# POWER.net
KiCad netlist of a schematic drawn in Altium Designer
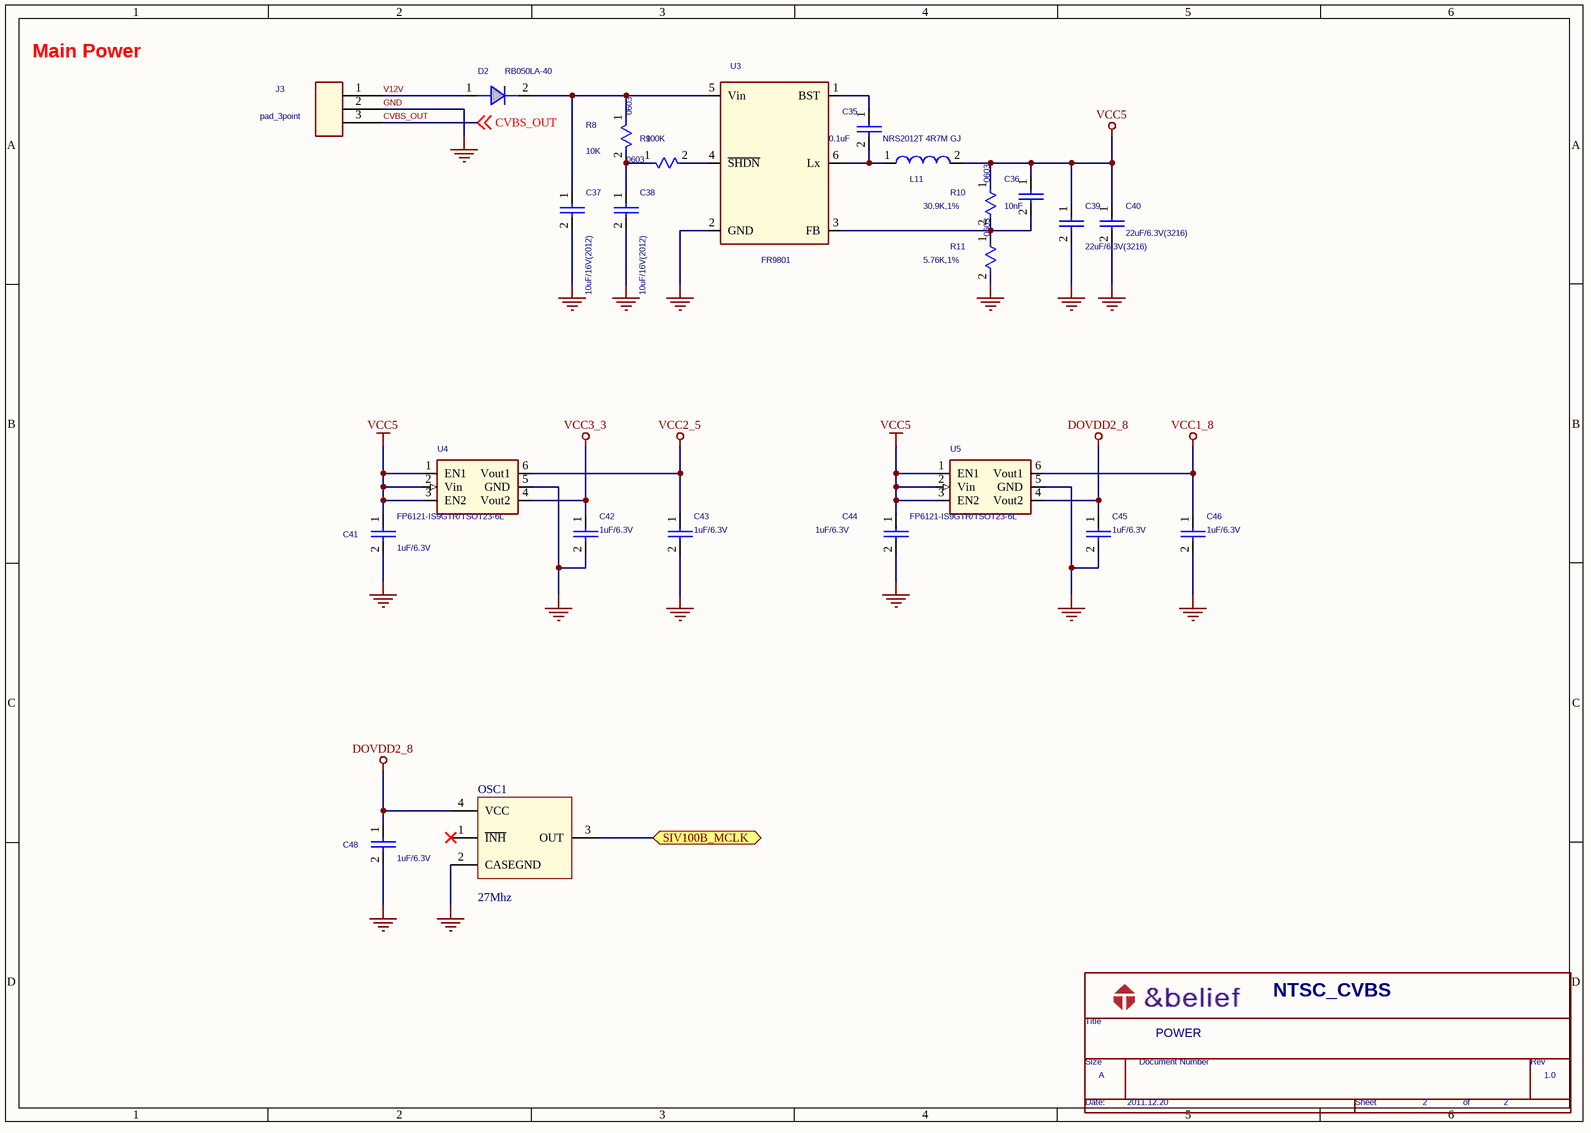
[diagram p0: POWER.SchDoc]

(export (version "E")
  (design (tool "Eeschema 10.0.6"))
  (components
    (comp (ref "C35") (value "0.1uF") (footprint "CAPC1005X55N") (libsource (lib "*") (part "CAP NP_16")))
    (comp (ref "C36") (value "10nF") (footprint "CAPC1005X55N") (libsource (lib "*") (part "CAP NP_13")))
    (comp (ref "C37")
      (value "10uF/16V(2012)")
      (footprint "CAPC2012X135N")
      (libsource (lib "*") (part "CAP NP_17"))
    )
    (comp (ref "C38")
      (value "10uF/16V(2012)")
      (footprint "CAPC2012X135N")
      (libsource (lib "*") (part "CAP NP_18"))
    )
    (comp (ref "C39")
      (value "22uF/6.3V(3216)")
      (footprint "CAPC3216X100N")
      (libsource (lib "*") (part "CAP NP_15"))
    )
    (comp (ref "C40")
      (value "22uF/6.3V(3216)")
      (footprint "CAPC3216X100N")
      (libsource (lib "*") (part "CAP NP_14"))
    )
    (comp (ref "C41") (value "1uF/6.3V") (footprint "CAPC1608X90N") (libsource (lib "*") (part "CAP NP_0")))
    (comp (ref "C42") (value "1uF/6.3V") (footprint "CAPC1608X90N") (libsource (lib "*") (part "CAP NP_1")))
    (comp (ref "C43") (value "1uF/6.3V") (footprint "CAPC1608X90N") (libsource (lib "*") (part "CAP NP_1")))
    (comp (ref "C44") (value "1uF/6.3V") (footprint "CAPC1608X90N") (libsource (lib "*") (part "CAP NP_0")))
    (comp (ref "C45") (value "1uF/6.3V") (footprint "CAPC1608X90N") (libsource (lib "*") (part "CAP NP_1")))
    (comp (ref "C46") (value "1uF/6.3V") (footprint "CAPC1608X90N") (libsource (lib "*") (part "CAP NP_1")))
    (comp (ref "C48") (value "1uF/6.3V") (footprint "CAPC1608X90N") (libsource (lib "*") (part "CAP NP_0")))
    (comp (ref "D2") (value "RB050LA-40") (footprint "RB50LA-40") (libsource (lib "*") (part "DIODE PIN_1")))
    (comp (ref "J3") (value "pad_3point") (footprint "Jump_3Way_Text1") (libsource (lib "*") (part "CON3")))
    (comp (ref "L11")
      (value "NRS2012T 4R7M GJ")
      (footprint "INDC2016X180N")
      (libsource (lib "*") (part "INDUCTOR_0"))
    )
    (comp (ref "OSC1")
      (value "27Mhz")
      (footprint "XTAL-4pin-3225")
      (description "OSC XO 50.000MHZ CMOS SMD")
      (libsource (lib "PBL - Resonators") (part "XO_50Mhz_3V3_50ppm_SMD"))
    )
    (comp (ref "R8")
      (value "10K")
      (footprint "RESC1005X40N")
      (description "0R,1/10W,5%,0603")
      (fields (field (name "TOLERANCE") "∮5%") (field (name "SIZE") "0603"))
      (libsource (lib "*") (part "0R,1/10W,5%,0603_0"))
    )
    (comp (ref "R9")
      (value "100K")
      (footprint "RESC1005X40N")
      (description "0R,1/10W,5%,0603")
      (fields (field (name "TOLERANCE") "∮5%") (field (name "SIZE") "0603"))
      (libsource (lib "*") (part "0R,1/10W,5%,0603_0"))
    )
    (comp (ref "R10")
      (value "30.9K,1%")
      (footprint "RESC1005X40N")
      (description "0R,1/10W,5%,0603")
      (fields (field (name "TOLERANCE") "∮5%") (field (name "SIZE") "0603"))
      (libsource (lib "*") (part "0R,1/10W,5%,0603_10"))
    )
    (comp (ref "R11")
      (value "5.76K,1%")
      (footprint "RESC1005X40N")
      (description "0R,1/10W,5%,0603")
      (fields (field (name "TOLERANCE") "∮5%") (field (name "SIZE") "0603"))
      (libsource (lib "*") (part "0R,1/10W,5%,0603_11"))
    )
    (comp (ref "U3") (value "FR9801") (footprint "SOT23-6") (libsource (lib "*") (part "R1244N001B_1")))
    (comp (ref "U4")
      (value "FP6121-IS9GTR/TSOT23-6L")
      (footprint "SOT23-6")
      (libsource (lib "*") (part "IC DC/DC RT8258 SOT26_0"))
    )
    (comp (ref "U5")
      (value "FP6121-IS9GTR/TSOT23-6L")
      (footprint "SOT23-6")
      (libsource (lib "*") (part "IC DC/DC RT8258 SOT26_0"))
    )
  )
  (nets
    (net (code "1") (name "/SIV100B_MCLK") (class "Default")
      (node (ref "OSC1") (pin "3") (pinfunction "OUT_3") (pintype "passive"))
    )
    (net (code "2") (name "/V12V") (class "Default")
      (node (ref "D2") (pin "1") (pinfunction "1_1") (pintype "passive"))
      (node (ref "J3") (pin "1") (pinfunction "1_1") (pintype "passive"))
    )
    (net (code "3") (name "CVBS_OUT") (class "Default")
      (node (ref "J3") (pin "3") (pinfunction "3_3") (pintype "passive"))
    )
    (net (code "4") (name "DOVDD2_8") (class "Default")
      (node (ref "C45") (pin "1") (pinfunction "1_1") (pintype "passive"))
      (node (ref "C48") (pin "1") (pinfunction "1_1") (pintype "passive"))
      (node (ref "OSC1") (pin "4") (pinfunction "VCC_4") (pintype "passive"))
      (node (ref "U5") (pin "4") (pinfunction "Vout2_4") (pintype "passive"))
    )
    (net (code "5") (name "GND") (class "Default")
      (node (ref "C37") (pin "2") (pinfunction "2_2") (pintype "passive"))
      (node (ref "C38") (pin "2") (pinfunction "2_2") (pintype "passive"))
      (node (ref "C39") (pin "2") (pinfunction "2_2") (pintype "passive"))
      (node (ref "C40") (pin "2") (pinfunction "2_2") (pintype "passive"))
      (node (ref "C41") (pin "2") (pinfunction "2_2") (pintype "passive"))
      (node (ref "C42") (pin "2") (pinfunction "2_2") (pintype "passive"))
      (node (ref "C43") (pin "2") (pinfunction "2_2") (pintype "passive"))
      (node (ref "C44") (pin "2") (pinfunction "2_2") (pintype "passive"))
      (node (ref "C45") (pin "2") (pinfunction "2_2") (pintype "passive"))
      (node (ref "C46") (pin "2") (pinfunction "2_2") (pintype "passive"))
      (node (ref "C48") (pin "2") (pinfunction "2_2") (pintype "passive"))
      (node (ref "J3") (pin "2") (pinfunction "2_2") (pintype "passive"))
      (node (ref "OSC1") (pin "2") (pinfunction "CASEGND_2") (pintype "passive"))
      (node (ref "R11") (pin "2") (pinfunction "2_2") (pintype "passive"))
      (node (ref "U3") (pin "2") (pinfunction "GND_2") (pintype "power_in"))
      (node (ref "U4") (pin "5") (pinfunction "GND_5") (pintype "passive"))
      (node (ref "U5") (pin "5") (pinfunction "GND_5") (pintype "passive"))
    )
    (net (code "6") (name "Net-(C38-Pad1)") (class "Default")
      (node (ref "C38") (pin "1") (pinfunction "1_1") (pintype "passive"))
      (node (ref "R8") (pin "2") (pinfunction "2_2") (pintype "passive"))
      (node (ref "R9") (pin "1") (pinfunction "1_1") (pintype "passive"))
    )
    (net (code "7") (name "Net-(U3-BST)") (class "Default")
      (node (ref "C35") (pin "1") (pinfunction "1_1") (pintype "passive"))
      (node (ref "U3") (pin "1") (pinfunction "BST_1") (pintype "passive"))
    )
    (net (code "8") (name "Net-(U3-FB)") (class "Default")
      (node (ref "C36") (pin "2") (pinfunction "2_2") (pintype "passive"))
      (node (ref "R10") (pin "2") (pinfunction "2_2") (pintype "passive"))
      (node (ref "R11") (pin "1") (pinfunction "1_1") (pintype "passive"))
      (node (ref "U3") (pin "3") (pinfunction "FB_3") (pintype "passive"))
    )
    (net (code "9") (name "Net-(U3-Lx)") (class "Default")
      (node (ref "C35") (pin "2") (pinfunction "2_2") (pintype "passive"))
      (node (ref "L11") (pin "1") (pinfunction "1_1") (pintype "passive"))
      (node (ref "U3") (pin "6") (pinfunction "Lx_6") (pintype "passive"))
    )
    (net (code "10") (name "Net-(U3-Vin)") (class "Default")
      (node (ref "C37") (pin "1") (pinfunction "1_1") (pintype "passive"))
      (node (ref "D2") (pin "2") (pinfunction "2_2") (pintype "passive"))
      (node (ref "R8") (pin "1") (pinfunction "1_1") (pintype "passive"))
      (node (ref "U3") (pin "5") (pinfunction "Vin_5") (pintype "power_in"))
    )
    (net (code "11") (name "Net-(U3-~{SHDN})") (class "Default")
      (node (ref "R9") (pin "2") (pinfunction "2_2") (pintype "passive"))
      (node (ref "U3") (pin "4") (pinfunction "~{SHDN}_4") (pintype "passive"))
    )
    (net (code "12") (name "VCC1_8") (class "Default")
      (node (ref "C46") (pin "1") (pinfunction "1_1") (pintype "passive"))
      (node (ref "U5") (pin "6") (pinfunction "Vout1_6") (pintype "passive"))
    )
    (net (code "13") (name "VCC2_5") (class "Default")
      (node (ref "C43") (pin "1") (pinfunction "1_1") (pintype "passive"))
      (node (ref "U4") (pin "6") (pinfunction "Vout1_6") (pintype "passive"))
    )
    (net (code "14") (name "VCC3_3") (class "Default")
      (node (ref "C42") (pin "1") (pinfunction "1_1") (pintype "passive"))
      (node (ref "U4") (pin "4") (pinfunction "Vout2_4") (pintype "passive"))
    )
    (net (code "15") (name "VCC5") (class "Default")
      (node (ref "C36") (pin "1") (pinfunction "1_1") (pintype "passive"))
      (node (ref "C39") (pin "1") (pinfunction "1_1") (pintype "passive"))
      (node (ref "C40") (pin "1") (pinfunction "1_1") (pintype "passive"))
      (node (ref "C41") (pin "1") (pinfunction "1_1") (pintype "passive"))
      (node (ref "C44") (pin "1") (pinfunction "1_1") (pintype "passive"))
      (node (ref "L11") (pin "2") (pinfunction "2_2") (pintype "passive"))
      (node (ref "R10") (pin "1") (pinfunction "1_1") (pintype "passive"))
      (node (ref "U4") (pin "1") (pinfunction "EN1_1") (pintype "passive"))
      (node (ref "U4") (pin "2") (pinfunction "Vin_2") (pintype "input"))
      (node (ref "U4") (pin "3") (pinfunction "EN2_3") (pintype "passive"))
      (node (ref "U5") (pin "1") (pinfunction "EN1_1") (pintype "passive"))
      (node (ref "U5") (pin "2") (pinfunction "Vin_2") (pintype "input"))
      (node (ref "U5") (pin "3") (pinfunction "EN2_3") (pintype "passive"))
    )
    (net (code "16") (name "unconnected-(OSC1-~{INH}-Pad1)") (class "Default")
      (node (ref "OSC1") (pin "1") (pinfunction "~{INH}_1") (pintype "passive+no_connect"))
    )
  )
)
